# AutoExhaustFan.net
KiCad netlist of a schematic drawn in EAGLE
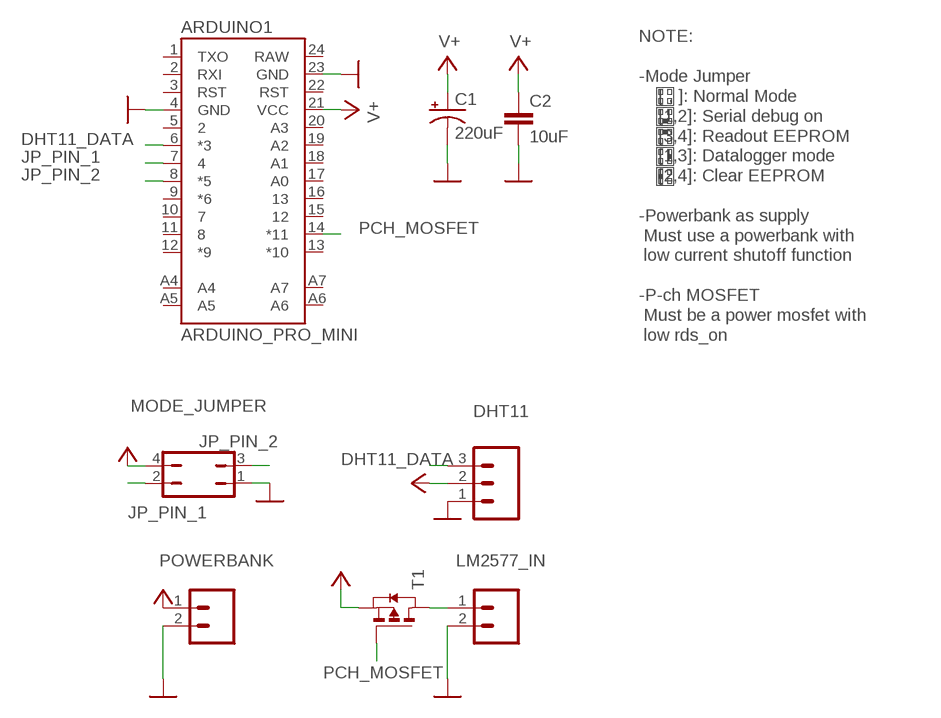
[diagram p0: schematic, sheet 1]

(export (version "E")
  (design (tool "Eeschema 10.0.6"))
  (components
    (comp (ref "ARDUINO1")
      (value "ARDUINO_PRO_MINI")
      (footprint "eagle-import:ARDUINO_PRO_MINI")
      (libsource (lib "eagle-import") (part "ARDUINO_PRO_MINI"))
    )
    (comp (ref "C1")
      (value "220uF")
      (footprint "eagle-import:CPOL-RADIAL-100UF-25V")
      (libsource (lib "eagle-import") (part "CAP_POLPTH1"))
    )
    (comp (ref "C2")
      (value "10uF")
      (footprint "eagle-import:1206")
      (libsource (lib "eagle-import") (part "CAP1206"))
    )
    (comp (ref "DHT11")
      (value "M03PTH")
      (footprint "eagle-import:1X03")
      (libsource (lib "eagle-import") (part "M03PTH"))
    )
    (comp (ref "LM2577_IN")
      (value "M02LOCK")
      (footprint "eagle-import:1X02_LOCK")
      (libsource (lib "eagle-import") (part "M02LOCK"))
    )
    (comp (ref "MODE_JUMPER")
      (value "JP2Q")
      (footprint "eagle-import:JP2Q")
      (libsource (lib "eagle-import") (part "JP2Q"))
    )
    (comp (ref "POWERBANK")
      (value "M02LOCK")
      (footprint "eagle-import:1X02_LOCK")
      (libsource (lib "eagle-import") (part "M02LOCK"))
    )
    (comp (ref "T1")
      (value "PMOSSOT23")
      (footprint "eagle-import:SOT-23")
      (libsource (lib "eagle-import") (part "PMOSSOT23"))
    )
  )
  (nets
    (net (code "1") (name "/DHT11_DATA") (class "Default")
      (node (ref "ARDUINO1") (pin "6") (pinfunction "*3_6") (pintype "bidirectional"))
      (node (ref "DHT11") (pin "3") (pinfunction "3_3") (pintype "passive"))
    )
    (net (code "2") (name "/JP_PIN_1") (class "Default")
      (node (ref "ARDUINO1") (pin "7") (pinfunction "4_7") (pintype "bidirectional"))
      (node (ref "MODE_JUMPER") (pin "2") (pinfunction "2_2") (pintype "passive"))
    )
    (net (code "3") (name "/JP_PIN_2") (class "Default")
      (node (ref "ARDUINO1") (pin "8") (pinfunction "*5_8") (pintype "bidirectional"))
      (node (ref "MODE_JUMPER") (pin "3") (pinfunction "3_3") (pintype "passive"))
    )
    (net (code "4") (name "/PCH_MOSFET") (class "Default")
      (node (ref "ARDUINO1") (pin "14") (pinfunction "*11_14") (pintype "bidirectional"))
      (node (ref "T1") (pin "3") (pinfunction "G_3") (pintype "passive"))
    )
    (net (code "5") (name "GND") (class "Default")
      (node (ref "ARDUINO1") (pin "23") (pinfunction "GND_23") (pintype "bidirectional"))
      (node (ref "ARDUINO1") (pin "4") (pinfunction "GND_4") (pintype "bidirectional"))
      (node (ref "C1") (pin "2") (pinfunction "-_2") (pintype "passive"))
      (node (ref "C2") (pin "2") (pinfunction "2_2") (pintype "passive"))
      (node (ref "DHT11") (pin "1") (pinfunction "1_1") (pintype "passive"))
      (node (ref "LM2577_IN") (pin "2") (pinfunction "2_2") (pintype "passive"))
      (node (ref "MODE_JUMPER") (pin "1") (pinfunction "1_1") (pintype "passive"))
      (node (ref "POWERBANK") (pin "2") (pinfunction "2_2") (pintype "passive"))
    )
    (net (code "6") (name "Net-(T1-D)") (class "Default")
      (node (ref "LM2577_IN") (pin "1") (pinfunction "1_1") (pintype "passive"))
      (node (ref "T1") (pin "1") (pinfunction "D_1") (pintype "passive"))
    )
    (net (code "7") (name "V+") (class "Default")
      (node (ref "ARDUINO1") (pin "21") (pinfunction "VCC_21") (pintype "bidirectional"))
      (node (ref "C1") (pin "1") (pinfunction "+_1") (pintype "passive"))
      (node (ref "C2") (pin "1") (pinfunction "1_1") (pintype "passive"))
      (node (ref "DHT11") (pin "2") (pinfunction "2_2") (pintype "passive"))
      (node (ref "MODE_JUMPER") (pin "4") (pinfunction "4_4") (pintype "passive"))
      (node (ref "POWERBANK") (pin "1") (pinfunction "1_1") (pintype "passive"))
      (node (ref "T1") (pin "2") (pinfunction "S_2") (pintype "passive"))
    )
    (net (code "8") (name "unconnected-(ARDUINO1-*6-Pad9)") (class "Default")
      (node (ref "ARDUINO1") (pin "9") (pinfunction "*6_9") (pintype "bidirectional"))
    )
    (net (code "9") (name "unconnected-(ARDUINO1-*9-Pad12)") (class "Default")
      (node (ref "ARDUINO1") (pin "12") (pinfunction "*9_12") (pintype "bidirectional"))
    )
    (net (code "10") (name "unconnected-(ARDUINO1-*10-Pad13)") (class "Default")
      (node (ref "ARDUINO1") (pin "13") (pinfunction "*10_13") (pintype "bidirectional"))
    )
    (net (code "11") (name "unconnected-(ARDUINO1-2-Pad5)") (class "Default")
      (node (ref "ARDUINO1") (pin "5") (pinfunction "2_5") (pintype "bidirectional"))
    )
    (net (code "12") (name "unconnected-(ARDUINO1-7-Pad10)") (class "Default")
      (node (ref "ARDUINO1") (pin "10") (pinfunction "7_10") (pintype "bidirectional"))
    )
    (net (code "13") (name "unconnected-(ARDUINO1-8-Pad11)") (class "Default")
      (node (ref "ARDUINO1") (pin "11") (pinfunction "8_11") (pintype "bidirectional"))
    )
    (net (code "14") (name "unconnected-(ARDUINO1-12-Pad15)") (class "Default")
      (node (ref "ARDUINO1") (pin "15") (pinfunction "12_15") (pintype "bidirectional"))
    )
    (net (code "15") (name "unconnected-(ARDUINO1-13-Pad16)") (class "Default")
      (node (ref "ARDUINO1") (pin "16") (pinfunction "13_16") (pintype "bidirectional"))
    )
    (net (code "16") (name "unconnected-(ARDUINO1-A0-Pad17)") (class "Default")
      (node (ref "ARDUINO1") (pin "17") (pinfunction "A0_17") (pintype "bidirectional"))
    )
    (net (code "17") (name "unconnected-(ARDUINO1-A1-Pad18)") (class "Default")
      (node (ref "ARDUINO1") (pin "18") (pinfunction "A1_18") (pintype "bidirectional"))
    )
    (net (code "18") (name "unconnected-(ARDUINO1-A2-Pad19)") (class "Default")
      (node (ref "ARDUINO1") (pin "19") (pinfunction "A2_19") (pintype "bidirectional"))
    )
    (net (code "19") (name "unconnected-(ARDUINO1-A3-Pad20)") (class "Default")
      (node (ref "ARDUINO1") (pin "20") (pinfunction "A3_20") (pintype "bidirectional"))
    )
    (net (code "20") (name "unconnected-(ARDUINO1-PadA4)") (class "Default")
      (node (ref "ARDUINO1") (pin "A4") (pinfunction "A4_A4") (pintype "bidirectional"))
    )
    (net (code "21") (name "unconnected-(ARDUINO1-PadA5)") (class "Default")
      (node (ref "ARDUINO1") (pin "A5") (pinfunction "A5_A5") (pintype "bidirectional"))
    )
    (net (code "22") (name "unconnected-(ARDUINO1-PadA6)") (class "Default")
      (node (ref "ARDUINO1") (pin "A6") (pinfunction "A6_A6") (pintype "bidirectional"))
    )
    (net (code "23") (name "unconnected-(ARDUINO1-PadA7)") (class "Default")
      (node (ref "ARDUINO1") (pin "A7") (pinfunction "A7_A7") (pintype "bidirectional"))
    )
    (net (code "24") (name "unconnected-(ARDUINO1-RAW-Pad24)") (class "Default")
      (node (ref "ARDUINO1") (pin "24") (pinfunction "RAW_24") (pintype "bidirectional"))
    )
    (net (code "25") (name "unconnected-(ARDUINO1-RST-Pad3)") (class "Default")
      (node (ref "ARDUINO1") (pin "3") (pinfunction "RST_3") (pintype "bidirectional"))
    )
    (net (code "26") (name "unconnected-(ARDUINO1-RST-Pad22)") (class "Default")
      (node (ref "ARDUINO1") (pin "22") (pinfunction "RST_22") (pintype "bidirectional"))
    )
    (net (code "27") (name "unconnected-(ARDUINO1-RXI-Pad2)") (class "Default")
      (node (ref "ARDUINO1") (pin "2") (pinfunction "RXI_2") (pintype "bidirectional"))
    )
    (net (code "28") (name "unconnected-(ARDUINO1-TXO-Pad1)") (class "Default")
      (node (ref "ARDUINO1") (pin "1") (pinfunction "TXO_1") (pintype "bidirectional"))
    )
  )
)
